# RS232.net
KiCad netlist of a schematic drawn in Altium Designer
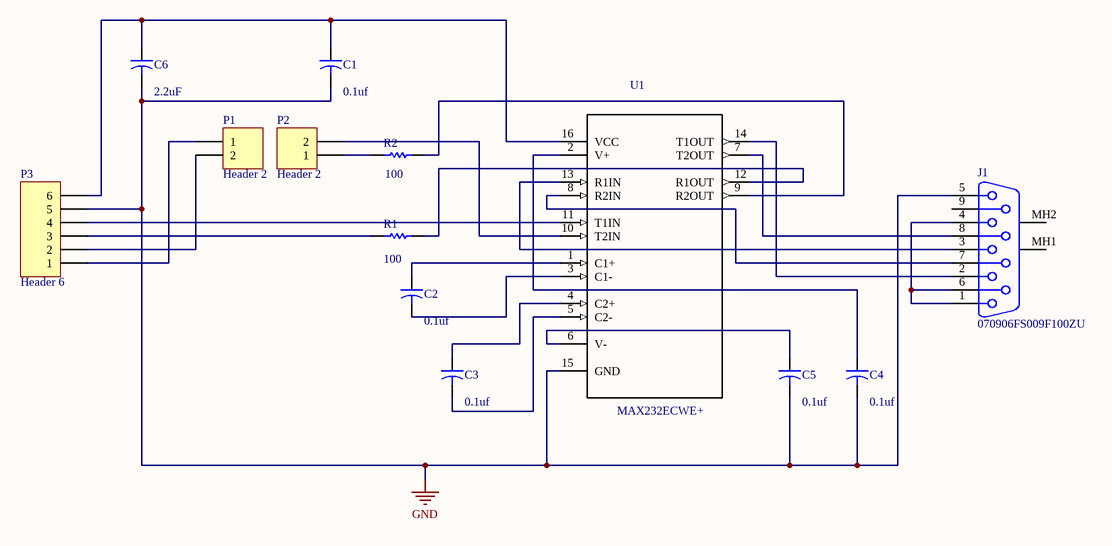
[diagram p0: RS232.SchDoc]

(export (version "E")
  (design (tool "Eeschema 10.0.6"))
  (components
    (comp (ref "C1")
      (value "0.1uf")
      (footprint "CAPR5-4X5")
      (description "Capacitor")
      (fields (field (name "Comment") "Cap2") (field (name "PUBLISHER") "Altium Limited"))
      (libsource (lib "Miscellaneous Devices") (part "Cap2"))
    )
    (comp (ref "C2")
      (value "0.1uf")
      (footprint "CAPR5-4X5")
      (description "Capacitor")
      (fields (field (name "PUBLISHER") "Altium Limited"))
      (libsource (lib "Miscellaneous Devices") (part "Cap2"))
    )
    (comp (ref "C3")
      (value "0.1uf")
      (footprint "CAPR5-4X5")
      (description "Capacitor")
      (fields (field (name "PUBLISHER") "Altium Limited"))
      (libsource (lib "Miscellaneous Devices") (part "Cap2"))
    )
    (comp (ref "C4")
      (value "0.1uf")
      (footprint "CAPR5-4X5")
      (description "Capacitor")
      (fields (field (name "PUBLISHER") "Altium Limited"))
      (libsource (lib "Miscellaneous Devices") (part "Cap2"))
    )
    (comp (ref "C5")
      (value "0.1uf")
      (footprint "CAPR5-4X5")
      (description "Capacitor")
      (fields (field (name "PUBLISHER") "Altium Limited"))
      (libsource (lib "Miscellaneous Devices") (part "Cap2"))
    )
    (comp (ref "C6")
      (value "Cap2")
      (footprint "CAPR5-4X5")
      (description "Capacitor")
      (fields (field (name "ALTIUM_UNNAMED_1") "2.2uF") (field (name "PUBLISHER") "Altium Limited"))
      (libsource (lib "Miscellaneous Devices") (part "Cap2"))
    )
    (comp (ref "J1")
      (value "070906FS009F100ZU")
      (footprint "070906FS009")
      (description "Ultra Thin D-Sub, Straight Dip Type, Female Connector, THT, 9 Position, 2.2mm Pin Length")
      (fields (field (name "PUBLISHER") "Altium Limited"))
      (libsource (lib "SUYIN D Subminiature") (part "070906FS009F100ZU"))
    )
    (comp (ref "P1")
      (value "Header 2")
      (footprint "HDR1X2")
      (description "Header, 2-Pin")
      (fields (field (name "PUBLISHER") "Altium Limited"))
      (libsource (lib "Miscellaneous Connectors") (part "Header 2"))
    )
    (comp (ref "P2")
      (value "Header 2")
      (footprint "HDR1X2")
      (description "Header, 2-Pin")
      (fields (field (name "PUBLISHER") "Altium Limited"))
      (libsource (lib "") (part "Header 2_1"))
    )
    (comp (ref "P3")
      (value "Header 6")
      (footprint "HDR1X6")
      (description "Header, 6-Pin")
      (fields (field (name "PUBLISHER") "Altium Limited"))
      (libsource (lib "Miscellaneous Connectors") (part "Header 6"))
    )
    (comp (ref "R1")
      (value "100")
      (footprint "AXIAL-0.3")
      (description "Resistor")
      (fields (field (name "Comment") "Res1") (field (name "PUBLISHER") "Altium Limited"))
      (libsource (lib "Miscellaneous Devices") (part "Res1"))
    )
    (comp (ref "R2")
      (value "100")
      (footprint "AXIAL-0.3")
      (description "Resistor")
      (fields (field (name "PUBLISHER") "Altium Limited"))
      (libsource (lib "Miscellaneous Devices") (part "Res1"))
    )
    (comp (ref "U1")
      (value "MAX232ECWE+")
      (footprint "SOIC127P1032X265-16N")
      (description "Dual Transmitter/Receiver RS-232 16-Pin SOIC W")
      (fields (field (name "MF") "Maxim Integrated") (field (name "DIGI-KEY_PART_NUMBER") "MAX232ECWE+-ND"))
      (libsource (lib "MAX232ECWE_") (part "MAX232ECWE+"))
    )
  )
  (nets
    (net (code "1") (name "GND") (class "Default")
      (node (ref "C1") (pin "2") (pinfunction "2_2") (pintype "passive"))
      (node (ref "C4") (pin "2") (pinfunction "2_2") (pintype "passive"))
      (node (ref "C5") (pin "2") (pinfunction "2_2") (pintype "passive"))
      (node (ref "C6") (pin "2") (pinfunction "2_2") (pintype "passive"))
      (node (ref "J1") (pin "5") (pinfunction "5_5") (pintype "passive"))
      (node (ref "P3") (pin "5") (pinfunction "5_5") (pintype "passive"))
      (node (ref "U1") (pin "15") (pinfunction "GND_15") (pintype "passive"))
    )
    (net (code "2") (name "Net-(J1-Pad1)") (class "Default")
      (node (ref "J1") (pin "1") (pinfunction "1_1") (pintype "passive"))
      (node (ref "J1") (pin "4") (pinfunction "4_4") (pintype "passive"))
      (node (ref "J1") (pin "6") (pinfunction "6_6") (pintype "passive"))
    )
    (net (code "3") (name "Net-(P1-Pad1)") (class "Default")
      (node (ref "P1") (pin "1") (pinfunction "1_1") (pintype "passive"))
      (node (ref "P3") (pin "1") (pinfunction "1_1") (pintype "passive"))
    )
    (net (code "4") (name "Net-(P1-Pad2)") (class "Default")
      (node (ref "P1") (pin "2") (pinfunction "2_2") (pintype "passive"))
      (node (ref "P3") (pin "2") (pinfunction "2_2") (pintype "passive"))
    )
    (net (code "5") (name "Net-(P2-Pad1)") (class "Default")
      (node (ref "P2") (pin "1") (pinfunction "1_1") (pintype "passive"))
      (node (ref "R2") (pin "1") (pinfunction "1_1") (pintype "passive"))
    )
    (net (code "6") (name "Net-(P3-Pad3)") (class "Default")
      (node (ref "P3") (pin "3") (pinfunction "3_3") (pintype "passive"))
      (node (ref "R1") (pin "1") (pinfunction "1_1") (pintype "passive"))
    )
    (net (code "7") (name "Net-(U1-C1+)") (class "Default")
      (node (ref "C2") (pin "1") (pinfunction "1_1") (pintype "passive"))
      (node (ref "U1") (pin "1") (pinfunction "C1+_1") (pintype "input"))
    )
    (net (code "8") (name "Net-(U1-C1-)") (class "Default")
      (node (ref "C2") (pin "2") (pinfunction "2_2") (pintype "passive"))
      (node (ref "U1") (pin "3") (pinfunction "C1-_3") (pintype "input"))
    )
    (net (code "9") (name "Net-(U1-C2+)") (class "Default")
      (node (ref "C3") (pin "1") (pinfunction "1_1") (pintype "passive"))
      (node (ref "U1") (pin "4") (pinfunction "C2+_4") (pintype "input"))
    )
    (net (code "10") (name "Net-(U1-C2-)") (class "Default")
      (node (ref "C3") (pin "2") (pinfunction "2_2") (pintype "passive"))
      (node (ref "U1") (pin "5") (pinfunction "C2-_5") (pintype "input"))
    )
    (net (code "11") (name "Net-(U1-R1IN)") (class "Default")
      (node (ref "J1") (pin "3") (pinfunction "3_3") (pintype "passive"))
      (node (ref "U1") (pin "13") (pinfunction "R1IN_13") (pintype "input"))
    )
    (net (code "12") (name "Net-(U1-R1OUT)") (class "Default")
      (node (ref "R1") (pin "2") (pinfunction "2_2") (pintype "passive"))
      (node (ref "U1") (pin "12") (pinfunction "R1OUT_12") (pintype "output"))
    )
    (net (code "13") (name "Net-(U1-R2IN)") (class "Default")
      (node (ref "J1") (pin "7") (pinfunction "7_7") (pintype "passive"))
      (node (ref "U1") (pin "8") (pinfunction "R2IN_8") (pintype "input"))
    )
    (net (code "14") (name "Net-(U1-R2OUT)") (class "Default")
      (node (ref "R2") (pin "2") (pinfunction "2_2") (pintype "passive"))
      (node (ref "U1") (pin "9") (pinfunction "R2OUT_9") (pintype "output"))
    )
    (net (code "15") (name "Net-(U1-T1IN)") (class "Default")
      (node (ref "P3") (pin "4") (pinfunction "4_4") (pintype "passive"))
      (node (ref "U1") (pin "11") (pinfunction "T1IN_11") (pintype "input"))
    )
    (net (code "16") (name "Net-(U1-T1OUT)") (class "Default")
      (node (ref "J1") (pin "2") (pinfunction "2_2") (pintype "passive"))
      (node (ref "U1") (pin "14") (pinfunction "T1OUT_14") (pintype "output"))
    )
    (net (code "17") (name "Net-(U1-T2IN)") (class "Default")
      (node (ref "P2") (pin "2") (pinfunction "2_2") (pintype "passive"))
      (node (ref "U1") (pin "10") (pinfunction "T2IN_10") (pintype "input"))
    )
    (net (code "18") (name "Net-(U1-T2OUT)") (class "Default")
      (node (ref "J1") (pin "8") (pinfunction "8_8") (pintype "passive"))
      (node (ref "U1") (pin "7") (pinfunction "T2OUT_7") (pintype "output"))
    )
    (net (code "19") (name "Net-(U1-V+)") (class "Default")
      (node (ref "C4") (pin "1") (pinfunction "1_1") (pintype "passive"))
      (node (ref "U1") (pin "2") (pinfunction "V+_2") (pintype "power_in"))
    )
    (net (code "20") (name "Net-(U1-V-)") (class "Default")
      (node (ref "C5") (pin "1") (pinfunction "1_1") (pintype "passive"))
      (node (ref "U1") (pin "6") (pinfunction "V-_6") (pintype "power_in"))
    )
    (net (code "21") (name "Net-(U1-VCC)") (class "Default")
      (node (ref "C1") (pin "1") (pinfunction "1_1") (pintype "passive"))
      (node (ref "C6") (pin "1") (pinfunction "1_1") (pintype "passive"))
      (node (ref "P3") (pin "6") (pinfunction "6_6") (pintype "passive"))
      (node (ref "U1") (pin "16") (pinfunction "VCC_16") (pintype "power_in"))
    )
    (net (code "22") (name "unconnected-(J1-Pad9)") (class "Default")
      (node (ref "J1") (pin "9") (pinfunction "9_9") (pintype "passive"))
    )
    (net (code "23") (name "unconnected-(J1-PadMH1)") (class "Default")
      (node (ref "J1") (pin "MH1") (pinfunction "MH1_MH1") (pintype "passive"))
    )
    (net (code "24") (name "unconnected-(J1-PadMH2)") (class "Default")
      (node (ref "J1") (pin "MH2") (pinfunction "MH2_MH2") (pintype "passive"))
    )
  )
)
